# Face_3Key1V0.net
KiCad netlist of a schematic drawn in Altium Designer
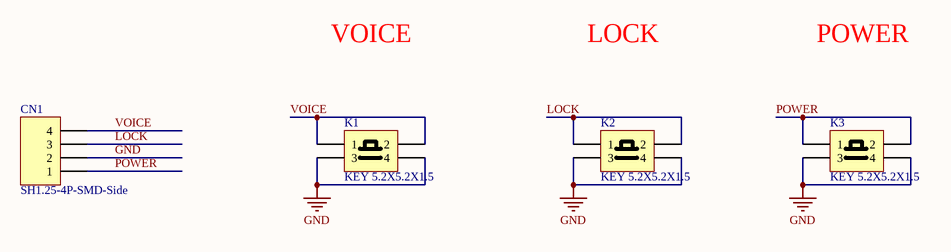
[diagram p0: Face_3Key1V0.SchDoc]

(export (version "E")
  (design (tool "Eeschema 10.0.6"))
  (components
    (comp (ref "CN1")
      (value "SH1.25-4P-SMD-TOP")
      (footprint "SH1.25_4P_SMd_SIDE")
      (fields (field (name "NAME1") "SH1.25-4P-SMD-Side"))
      (libsource (lib "LM") (part "Header4"))
    )
    (comp (ref "K1")
      (value "KEY 5.2X5.2X1.5")
      (footprint "5.2X5.2X1.5 TACT SWITCH")
      (description "5.2X5.2X1.5 TACT SWITCH")
      (fields (field (name "PUBLISHER") "Altium Limited"))
      (libsource (lib "LM") (part "Tactile Switch KEY6x6x14"))
    )
    (comp (ref "K2")
      (value "KEY 5.2X5.2X1.5")
      (footprint "5.2X5.2X1.5 TACT SWITCH")
      (description "5.2X5.2X1.5 TACT SWITCH")
      (fields (field (name "PUBLISHER") "Altium Limited"))
      (libsource (lib "LM") (part "Tactile Switch KEY6x6x14"))
    )
    (comp (ref "K3")
      (value "KEY 5.2X5.2X1.5")
      (footprint "5.2X5.2X1.5 TACT SWITCH")
      (description "5.2X5.2X1.5 TACT SWITCH")
      (fields (field (name "PUBLISHER") "Altium Limited"))
      (libsource (lib "LM") (part "Tactile Switch KEY6x6x14"))
    )
  )
  (nets
    (net (code "1") (name "/LOCK") (class "Default")
      (node (ref "CN1") (pin "3") (pinfunction "3_3") (pintype "passive"))
      (node (ref "K2") (pin "1") (pinfunction "1_1") (pintype "passive"))
      (node (ref "K2") (pin "2") (pinfunction "2_2") (pintype "passive"))
    )
    (net (code "2") (name "/POWER") (class "Default")
      (node (ref "CN1") (pin "1") (pinfunction "1_1") (pintype "passive"))
      (node (ref "K3") (pin "1") (pinfunction "1_1") (pintype "passive"))
      (node (ref "K3") (pin "2") (pinfunction "2_2") (pintype "passive"))
    )
    (net (code "3") (name "/VOICE") (class "Default")
      (node (ref "CN1") (pin "4") (pinfunction "4_4") (pintype "passive"))
      (node (ref "K1") (pin "1") (pinfunction "1_1") (pintype "passive"))
      (node (ref "K1") (pin "2") (pinfunction "2_2") (pintype "passive"))
    )
    (net (code "4") (name "GND") (class "Default")
      (node (ref "CN1") (pin "2") (pinfunction "2_2") (pintype "passive"))
      (node (ref "K1") (pin "3") (pinfunction "3_3") (pintype "passive"))
      (node (ref "K1") (pin "4") (pinfunction "4_4") (pintype "passive"))
      (node (ref "K2") (pin "3") (pinfunction "3_3") (pintype "passive"))
      (node (ref "K2") (pin "4") (pinfunction "4_4") (pintype "passive"))
      (node (ref "K3") (pin "3") (pinfunction "3_3") (pintype "passive"))
      (node (ref "K3") (pin "4") (pinfunction "4_4") (pintype "passive"))
    )
  )
)
